# Power_Supplies.net
KiCad netlist of a schematic drawn in Altium Designer
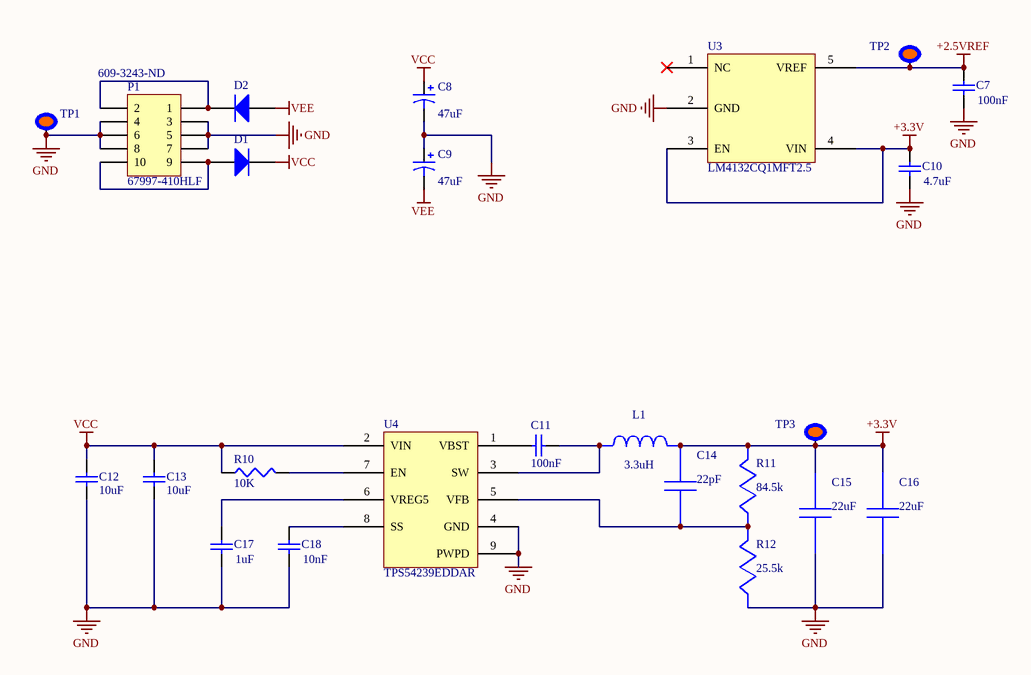
[diagram p0: Power Supplies.SchDoc]

(export (version "E")
  (design (tool "Eeschema 10.0.6"))
  (components
    (comp (ref "C7")
      (value "100nF")
      (footprint "RES_0603")
      (description "Capacitor")
      (fields
        (field (name "MANUFACTURER") "AVX Corporation")
        (field (name "MANUFACTURER PART NUMBER") "06035G104ZAT2A")
      )
      (libsource (lib "Miscellaneous Devices") (part "Cap"))
    )
    (comp (ref "C8")
      (value "47uF")
      (footprint "CAPAE_UW_J_6.3mm")
      (description "Polarized Capacitor (Surface Mount)")
      (fields
        (field (name "MANUFACTURER") "Panasonic")
        (field (name "MANUFACTURER PART NUMBER") "EEE-FK1V470P")
      )
      (libsource (lib "Miscellaneous Devices") (part "Cap Pol3"))
    )
    (comp (ref "C9")
      (value "47uF")
      (footprint "CAPAE_UW_J_6.3mm")
      (description "Polarized Capacitor (Surface Mount)")
      (fields
        (field (name "MANUFACTURER") "Panasonic")
        (field (name "MANUFACTURER PART NUMBER") "EEE-FK1V470P")
      )
      (libsource (lib "Miscellaneous Devices") (part "Cap Pol3"))
    )
    (comp (ref "C10")
      (value "4.7uF")
      (footprint "RES_0805")
      (description "Capacitor")
      (fields
        (field (name "MANUFACTURER") "Samsung Electro-Mechanics")
        (field (name "MANUFACTURER PART NUMBER") "CL21A475KACLRNC")
      )
      (libsource (lib "Miscellaneous Devices") (part "Cap"))
    )
    (comp (ref "C11")
      (value "100nF")
      (footprint "RES_0603")
      (description "Capacitor")
      (fields
        (field (name "MANUFACTURER") "AVX Corporation")
        (field (name "MANUFACTURER PART NUMBER") "06035G104ZAT2A")
      )
      (libsource (lib "Miscellaneous Devices") (part "Cap"))
    )
    (comp (ref "C12")
      (value "10uF")
      (footprint "RES_1206")
      (description "Capacitor")
      (fields
        (field (name "MANUFACTURER") "Murata")
        (field (name "MANUFACTURER PART NUMBER") "GRT31CR61H106ME01L")
      )
      (libsource (lib "Miscellaneous Devices") (part "Cap"))
    )
    (comp (ref "C13")
      (value "10uF")
      (footprint "RES_1206")
      (description "Capacitor")
      (fields
        (field (name "MANUFACTURER") "Murata")
        (field (name "MANUFACTURER PART NUMBER") "GRT31CR61H106ME01L")
      )
      (libsource (lib "Miscellaneous Devices") (part "Cap"))
    )
    (comp (ref "C14")
      (value "22pF")
      (footprint "RES_0603")
      (description "Capacitor")
      (fields
        (field (name "MANUFACTURER PART NUMBER") "C0603C220J5GACTU")
        (field (name "MANUFACTURER") "KEMET")
      )
      (libsource (lib "TI WEBENCH") (part "Cff"))
    )
    (comp (ref "C15")
      (value "22uF")
      (footprint "RES_0805")
      (description "Capacitor")
      (fields
        (field (name "MANUFACTURER PART NUMBER") "CL21A226KPCLRNC")
        (field (name "MANUFACTURER") "Samsung Electro-Mechanics")
      )
      (libsource (lib "TI WEBENCH") (part "Cout"))
    )
    (comp (ref "C16")
      (value "22uF")
      (footprint "RES_0805")
      (description "Capacitor")
      (fields
        (field (name "MANUFACTURER PART NUMBER") "CL21A226KPCLRNC")
        (field (name "MANUFACTURER") "Samsung Electro-Mechanics")
      )
      (libsource (lib "TI WEBENCH") (part "Cout"))
    )
    (comp (ref "C17")
      (value "1uF")
      (footprint "RES_0603")
      (description "Capacitor")
      (fields
        (field (name "MANUFACTURER") "Samsung Electro-Mechanics")
        (field (name "MANUFACTURER PART NUMBER") "CL10A105KA8NNNC")
      )
      (libsource (lib "Miscellaneous Devices") (part "Cap"))
    )
    (comp (ref "C18")
      (value "10nF")
      (footprint "RES_0603")
      (description "Capacitor")
      (fields
        (field (name "MANUFACTURER") "Samsung Electro-Mechanics")
        (field (name "MANUFACTURER PART NUMBER") "CL10B103KB8NCNC")
      )
      (libsource (lib "Miscellaneous Devices") (part "Cap"))
    )
    (comp (ref "D1")
      (value "1N5819HW-7-F")
      (footprint "SOD123")
      (description "Default Diode")
      (fields (field (name "MANUFACTURER") "Diodes Incorporated"))
      (libsource (lib "Miscellaneous Devices") (part "Diode"))
    )
    (comp (ref "D2")
      (value "1N5819HW-7-F")
      (footprint "SOD123")
      (description "Default Diode")
      (fields (field (name "MANUFACTURER") "Diodes Incorporated"))
      (libsource (lib "Miscellaneous Devices") (part "Diode"))
    )
    (comp (ref "L1")
      (value "3.3uH")
      (footprint "INDPM6060X450N")
      (description "Inductor")
      (fields (field (name "MANUFACTURER PART NUMBER") "VLS6045EX-3R3N") (field (name "MANUFACTURER") "TDK"))
      (libsource (lib "TI WEBENCH") (part "L1"))
    )
    (comp (ref "P1")
      (value "67997-410HLF")
      (footprint "HDR2X5")
      (description "Header, 5-Pin, Dual row")
      (fields
        (field (name "MANUFACTURER") "Amphenol FCI")
        (field (name "SUPPLIER PART NUMBER 1") "609-3243-ND")
      )
      (libsource (lib "Miscellaneous Connectors") (part "Header 5X2"))
    )
    (comp (ref "R10")
      (value "10K")
      (footprint "RES_0805")
      (description "Resistor")
      (fields
        (field (name "MANUFACTURER") "Susumu")
        (field (name "MANUFACTURER PART NUMBER") "RR1220P-103-D")
      )
      (libsource (lib "Miscellaneous Devices") (part "Res3"))
    )
    (comp (ref "R11")
      (value "84.5k")
      (footprint "RES_0603")
      (description "Resistor")
      (fields
        (field (name "MANUFACTURER PART NUMBER") "ERA-3AEB8452V")
        (field (name "MANUFACTURER") "Panasonic Electronic Components")
      )
      (libsource (lib "TI WEBENCH") (part "Rfbt"))
    )
    (comp (ref "R12")
      (value "25.5k")
      (footprint "RES_0603")
      (description "Resistor")
      (fields
        (field (name "MANUFACTURER PART NUMBER") "ERA-3AEB2552V")
        (field (name "MANUFACTURER") "Panasonic Electronic Components")
      )
      (libsource (lib "TI WEBENCH") (part "Rfbb"))
    )
    (comp (ref "TP1")
      (value "loop test point")
      (footprint "Test Point Mt Hole")
      (description "Test Point Loop Miniature Keysone")
      (fields
        (field (name "MANUFACTURER") "Keystone Electronics")
        (field (name "MANUFACTURER PART NUMBER") "5003")
      )
      (libsource (lib "Custom") (part "Test Point"))
    )
    (comp (ref "TP2")
      (value "loop test point")
      (footprint "Test Point Mt Hole")
      (description "Test Point Loop Miniature Keysone")
      (fields
        (field (name "MANUFACTURER") "Keystone Electronics")
        (field (name "MANUFACTURER PART NUMBER") "5003")
      )
      (libsource (lib "Custom") (part "Test Point"))
    )
    (comp (ref "TP3")
      (value "loop test point")
      (footprint "Test Point Mt Hole")
      (description "Test Point Loop Miniature Keysone")
      (fields
        (field (name "MANUFACTURER") "Keystone Electronics")
        (field (name "MANUFACTURER PART NUMBER") "5003")
      )
      (libsource (lib "Custom") (part "Test Point"))
    )
    (comp (ref "U3")
      (value "LM4132CQ1MFT2.5")
      (footprint "LM4132CQ1MFT2.5")
      (description "Precision Low Dropout 2.5V Reference")
      (fields (field (name "MANUFACTURER") "Texas Instruments"))
      (libsource (lib "Custom") (part "LM4132"))
    )
    (comp (ref "U4")
      (value "TPS54239EDDAR")
      (footprint "DDA")
      (description "4.5V to 23V Input, 2-A Synchronous Step-Down SWIFT™ Converter With Eco-mode")
      (fields (field (name "MANUFACTURER") "Texas Instruments"))
      (libsource (lib "Custom") (part "TPS54239EDDA"))
    )
  )
  (nets
    (net (code "1") (name "+2.5VREF") (class "Default")
      (node (ref "C7") (pin "2") (pinfunction "2_2") (pintype "passive"))
      (node (ref "TP2") (pin "1") (pinfunction "1_1") (pintype "passive"))
      (node (ref "U3") (pin "5") (pinfunction "VREF_5") (pintype "passive"))
    )
    (net (code "2") (name "+3.3V") (class "Default")
      (node (ref "C10") (pin "2") (pinfunction "2_2") (pintype "passive"))
      (node (ref "C14") (pin "1") (pinfunction "1_1") (pintype "passive"))
      (node (ref "C15") (pin "1") (pinfunction "1_1") (pintype "passive"))
      (node (ref "C16") (pin "1") (pinfunction "1_1") (pintype "passive"))
      (node (ref "L1") (pin "1") (pinfunction "1_1") (pintype "passive"))
      (node (ref "R11") (pin "1") (pinfunction "1_1") (pintype "passive"))
      (node (ref "TP3") (pin "1") (pinfunction "1_1") (pintype "passive"))
      (node (ref "U3") (pin "3") (pinfunction "EN_3") (pintype "passive"))
      (node (ref "U3") (pin "4") (pinfunction "VIN_4") (pintype "passive"))
    )
    (net (code "3") (name "GND") (class "Default")
      (node (ref "C10") (pin "1") (pinfunction "1_1") (pintype "passive"))
      (node (ref "C12") (pin "2") (pinfunction "2_2") (pintype "passive"))
      (node (ref "C13") (pin "2") (pinfunction "2_2") (pintype "passive"))
      (node (ref "C15") (pin "2") (pinfunction "2_2") (pintype "passive"))
      (node (ref "C16") (pin "2") (pinfunction "2_2") (pintype "passive"))
      (node (ref "C17") (pin "1") (pinfunction "1_1") (pintype "passive"))
      (node (ref "C18") (pin "1") (pinfunction "1_1") (pintype "passive"))
      (node (ref "C7") (pin "1") (pinfunction "1_1") (pintype "passive"))
      (node (ref "C8") (pin "2") (pinfunction "2_2") (pintype "passive"))
      (node (ref "C9") (pin "1") (pinfunction "1_1") (pintype "passive"))
      (node (ref "P1") (pin "3") (pinfunction "3_3") (pintype "passive"))
      (node (ref "P1") (pin "4") (pinfunction "4_4") (pintype "passive"))
      (node (ref "P1") (pin "5") (pinfunction "5_5") (pintype "passive"))
      (node (ref "P1") (pin "6") (pinfunction "6_6") (pintype "passive"))
      (node (ref "P1") (pin "7") (pinfunction "7_7") (pintype "passive"))
      (node (ref "P1") (pin "8") (pinfunction "8_8") (pintype "passive"))
      (node (ref "R12") (pin "2") (pinfunction "2_2") (pintype "passive"))
      (node (ref "TP1") (pin "1") (pinfunction "1_1") (pintype "passive"))
      (node (ref "U3") (pin "2") (pinfunction "GND_2") (pintype "passive"))
      (node (ref "U4") (pin "4") (pinfunction "GND_4") (pintype "passive"))
      (node (ref "U4") (pin "9") (pinfunction "PWPD_9") (pintype "passive"))
    )
    (net (code "4") (name "Net-(D1-A)") (class "Default")
      (node (ref "D1") (pin "1") (pinfunction "A_1") (pintype "passive"))
      (node (ref "P1") (pin "10") (pinfunction "10_10") (pintype "passive"))
      (node (ref "P1") (pin "9") (pinfunction "9_9") (pintype "passive"))
    )
    (net (code "5") (name "Net-(D2-K)") (class "Default")
      (node (ref "D2") (pin "2") (pinfunction "K_2") (pintype "passive"))
      (node (ref "P1") (pin "1") (pinfunction "1_1") (pintype "passive"))
      (node (ref "P1") (pin "2") (pinfunction "2_2") (pintype "passive"))
    )
    (net (code "6") (name "Net-(U4-EN)") (class "Default")
      (node (ref "R10") (pin "2") (pinfunction "2_2") (pintype "passive"))
      (node (ref "U4") (pin "7") (pinfunction "EN_7") (pintype "passive"))
    )
    (net (code "7") (name "Net-(U4-SS)") (class "Default")
      (node (ref "C18") (pin "2") (pinfunction "2_2") (pintype "passive"))
      (node (ref "U4") (pin "8") (pinfunction "SS_8") (pintype "passive"))
    )
    (net (code "8") (name "Net-(U4-SW)") (class "Default")
      (node (ref "C11") (pin "1") (pinfunction "1_1") (pintype "passive"))
      (node (ref "L1") (pin "2") (pinfunction "2_2") (pintype "passive"))
      (node (ref "U4") (pin "3") (pinfunction "SW_3") (pintype "passive"))
    )
    (net (code "9") (name "Net-(U4-VBST)") (class "Default")
      (node (ref "C11") (pin "2") (pinfunction "2_2") (pintype "passive"))
      (node (ref "U4") (pin "1") (pinfunction "VBST_1") (pintype "passive"))
    )
    (net (code "10") (name "Net-(U4-VFB)") (class "Default")
      (node (ref "C14") (pin "2") (pinfunction "2_2") (pintype "passive"))
      (node (ref "R11") (pin "2") (pinfunction "2_2") (pintype "passive"))
      (node (ref "R12") (pin "1") (pinfunction "1_1") (pintype "passive"))
      (node (ref "U4") (pin "5") (pinfunction "VFB_5") (pintype "passive"))
    )
    (net (code "11") (name "Net-(U4-VREG5)") (class "Default")
      (node (ref "C17") (pin "2") (pinfunction "2_2") (pintype "passive"))
      (node (ref "U4") (pin "6") (pinfunction "VREG5_6") (pintype "passive"))
    )
    (net (code "12") (name "VCC") (class "Default")
      (node (ref "C12") (pin "1") (pinfunction "1_1") (pintype "passive"))
      (node (ref "C13") (pin "1") (pinfunction "1_1") (pintype "passive"))
      (node (ref "C8") (pin "1") (pinfunction "1_1") (pintype "passive"))
      (node (ref "D1") (pin "2") (pinfunction "K_2") (pintype "passive"))
      (node (ref "R10") (pin "1") (pinfunction "1_1") (pintype "passive"))
      (node (ref "U4") (pin "2") (pinfunction "VIN_2") (pintype "passive"))
    )
    (net (code "13") (name "VEE") (class "Default")
      (node (ref "C9") (pin "2") (pinfunction "2_2") (pintype "passive"))
      (node (ref "D2") (pin "1") (pinfunction "A_1") (pintype "passive"))
    )
    (net (code "14") (name "unconnected-(U3-NC-Pad1)") (class "Default")
      (node (ref "U3") (pin "1") (pinfunction "NC_1") (pintype "passive+no_connect"))
    )
  )
)
